# Sheet1.net
KiCad netlist of a schematic drawn in Altium Designer
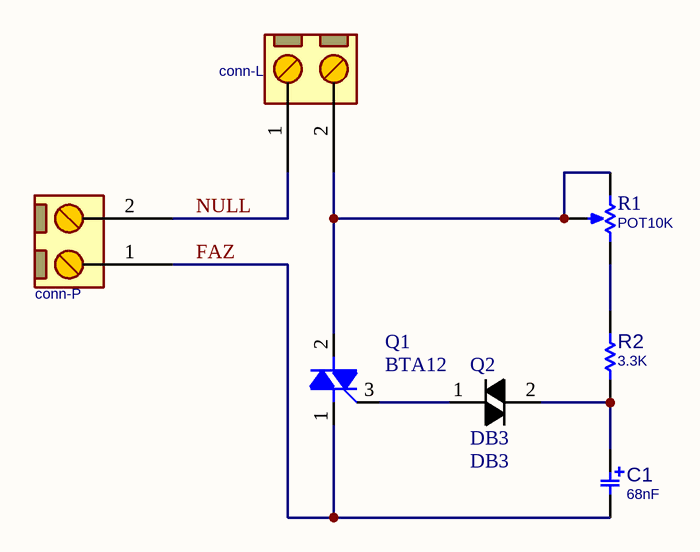
[diagram p0: Sheet1.SchDoc]

(export (version "E")
  (design (tool "Eeschema 10.0.6"))
  (components
    (comp (ref "C1")
      (value "68nF")
      (footprint "C_FLM_7X5H11")
      (description "CAP, THD, FILM,")
      (fields (field (name "MANF_P#") "MANF_PART#") (field (name "MANF") "MANF"))
      (libsource (lib "passive_thd") (part "CAP_THD_FLM"))
    )
    (comp (ref "conn-L")
      (value "CONN_TB2")
      (footprint "MSTB_2")
      (description "CONN, PHOENIX MSTB, 5-G, 5.08mm pitch")
      (libsource (lib "") (part "CONN_MSTB_2_1"))
    )
    (comp (ref "conn-P")
      (value "CONN_TB2")
      (footprint "MSTB_2")
      (description "CONN, PHOENIX MSTB, 5-G, 5.08mm pitch")
      (libsource (lib "conn_terminalB") (part "CONN_MSTB_2"))
    )
    (comp (ref "Q1")
      (value "BTA12")
      (footprint "TO220_3")
      (description "Triac, 600V, 12A, TO-220")
      (fields (field (name "MANF_P#") "BTA12-600BW, BTA12-600CW, BTA12-600TW") (field (name "MANF") "ST"))
      (libsource (lib "triac_diac") (part "TRIAC_BTA12-600_TO220"))
    )
    (comp (ref "Q2")
      (value "DB3")
      (footprint "D_AX03_DO35")
      (description "Diac, 32VBO, DO-35")
      (fields (field (name "MANF") "ST") (field (name "ALTIUM_VALUE") "DB3"))
      (libsource (lib "triac_diac") (part "DIAC_DB3_DO35"))
    )
    (comp (ref "R1")
      (value "POT10K")
      (footprint "VOL_R")
      (description "RESISTOR, THD, Potentiometer Volume")
      (libsource (lib "resistor_pot_trimmer") (part "RES_THD_POT_VOL"))
    )
    (comp (ref "R2")
      (value "3.3K")
      (footprint "R025W_AX04")
      (description "RESISTOR, THD")
      (fields (field (name "MANF_P#") "RK73H1ETTP4701F") (field (name "MANF") "KOA SPEER"))
      (libsource (lib "passive_thd") (part "RES_THD"))
    )
  )
  (nets
    (net (code "1") (name "/FAZ") (class "Default")
      (node (ref "C1") (pin "2") (pinfunction "2_2") (pintype "passive"))
      (node (ref "Q1") (pin "1") (pinfunction "T1_1") (pintype "passive"))
      (node (ref "conn-P") (pin "1") (pinfunction "1_1") (pintype "passive"))
    )
    (net (code "2") (name "/NULL") (class "Default")
      (node (ref "conn-L") (pin "1") (pinfunction "1_1") (pintype "passive"))
      (node (ref "conn-P") (pin "2") (pinfunction "2_2") (pintype "passive"))
    )
    (net (code "3") (name "Net-(Q1-G)") (class "Default")
      (node (ref "Q1") (pin "3") (pinfunction "G_3") (pintype "passive"))
      (node (ref "Q2") (pin "1") (pinfunction "A1_1") (pintype "passive"))
    )
    (net (code "4") (name "Net-(Q1-T2)") (class "Default")
      (node (ref "Q1") (pin "2") (pinfunction "T2_2") (pintype "passive"))
      (node (ref "R1") (pin "1") (pinfunction "TOP_1") (pintype "passive"))
      (node (ref "R1") (pin "2") (pinfunction "TAP_2") (pintype "passive"))
      (node (ref "conn-L") (pin "2") (pinfunction "2_2") (pintype "passive"))
    )
    (net (code "5") (name "Net-(Q2-A2)") (class "Default")
      (node (ref "C1") (pin "1") (pinfunction "1_1") (pintype "passive"))
      (node (ref "Q2") (pin "2") (pinfunction "A2_2") (pintype "passive"))
      (node (ref "R2") (pin "1") (pinfunction "1_1") (pintype "passive"))
    )
    (net (code "6") (name "Net-(R1-BOT)") (class "Default")
      (node (ref "R1") (pin "3") (pinfunction "BOT_3") (pintype "passive"))
      (node (ref "R2") (pin "2") (pinfunction "2_2") (pintype "passive"))
    )
  )
)
